# Atari_2600_PP.net
KiCad netlist of a schematic drawn in EAGLE
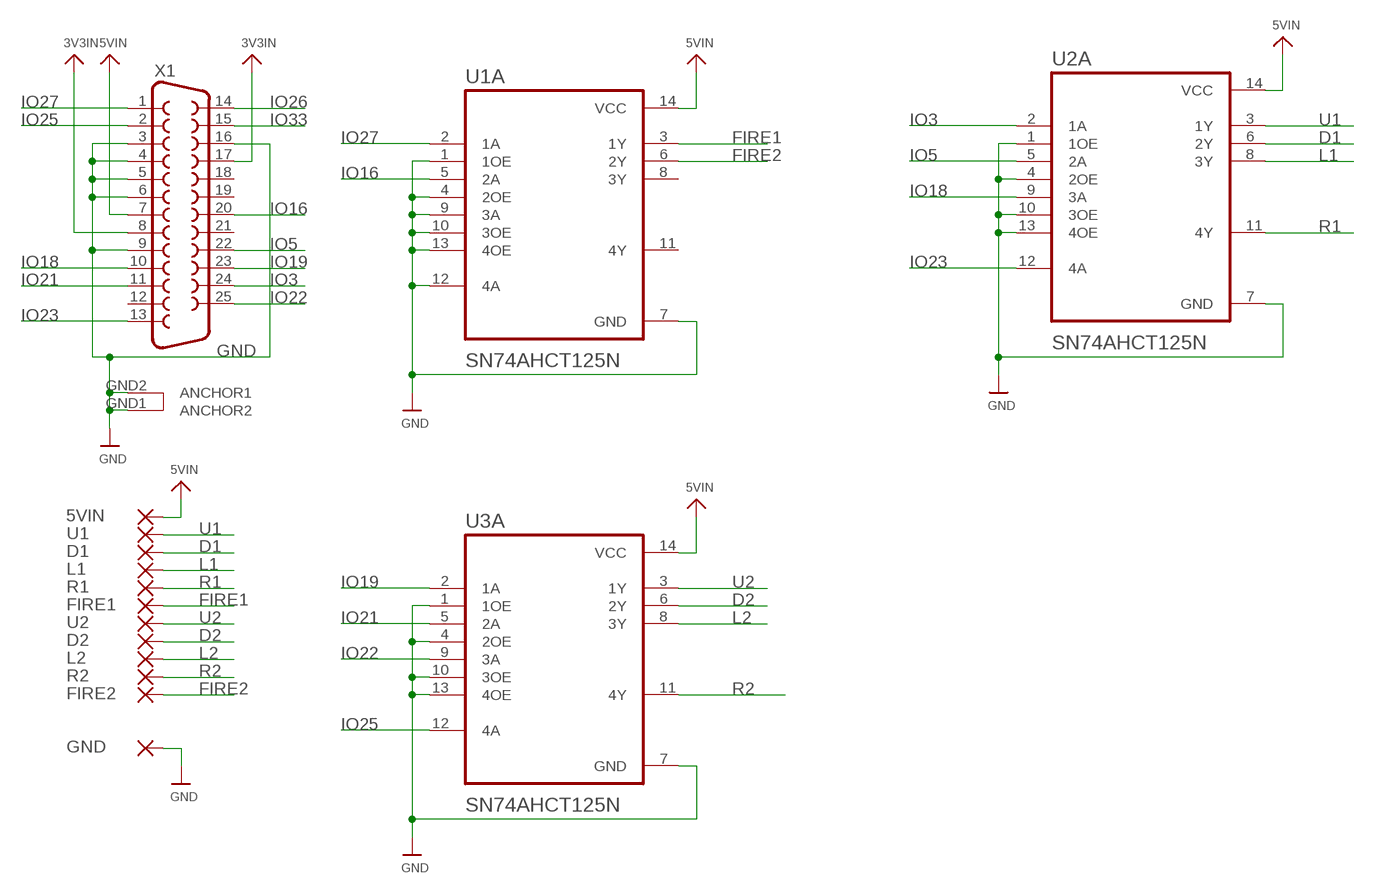
[diagram p0: schematic, sheet 1]

(export (version "E")
  (design (tool "Eeschema 10.0.6"))
  (components
    (comp (ref "5VIN")
      (value "SMD5")
      (footprint "eagle-import:SMD2,54-5,08")
      (libsource (lib "eagle-import") (part "SMD5"))
    )
    (comp (ref "D1")
      (value "SMD5")
      (footprint "eagle-import:SMD2,54-5,08")
      (libsource (lib "eagle-import") (part "SMD5"))
    )
    (comp (ref "D2")
      (value "SMD5")
      (footprint "eagle-import:SMD2,54-5,08")
      (libsource (lib "eagle-import") (part "SMD5"))
    )
    (comp (ref "FIRE1")
      (value "SMD5")
      (footprint "eagle-import:SMD2,54-5,08")
      (libsource (lib "eagle-import") (part "SMD5"))
    )
    (comp (ref "FIRE2")
      (value "SMD5")
      (footprint "eagle-import:SMD2,54-5,08")
      (libsource (lib "eagle-import") (part "SMD5"))
    )
    (comp (ref "GND")
      (value "SMD5")
      (footprint "eagle-import:SMD2,54-5,08")
      (libsource (lib "eagle-import") (part "SMD5"))
    )
    (comp (ref "L1")
      (value "SMD5")
      (footprint "eagle-import:SMD2,54-5,08")
      (libsource (lib "eagle-import") (part "SMD5"))
    )
    (comp (ref "L2")
      (value "SMD5")
      (footprint "eagle-import:SMD2,54-5,08")
      (libsource (lib "eagle-import") (part "SMD5"))
    )
    (comp (ref "R1")
      (value "SMD5")
      (footprint "eagle-import:SMD2,54-5,08")
      (libsource (lib "eagle-import") (part "SMD5"))
    )
    (comp (ref "R2")
      (value "SMD5")
      (footprint "eagle-import:SMD2,54-5,08")
      (libsource (lib "eagle-import") (part "SMD5"))
    )
    (comp (ref "U1")
      (value "SMD5")
      (footprint "eagle-import:SMD2,54-5,08")
      (libsource (lib "eagle-import") (part "SMD5"))
    )
    (comp (ref "U1A")
      (value "SN74AHCT125N")
      (footprint "eagle-import:DIP794W45P254L1969H508Q14")
      (fields (field (name "MF") "Texas Instruments"))
      (libsource (lib "eagle-import") (part "SN74AHCT125N"))
    )
    (comp (ref "U2")
      (value "SMD5")
      (footprint "eagle-import:SMD2,54-5,08")
      (libsource (lib "eagle-import") (part "SMD5"))
    )
    (comp (ref "U2A")
      (value "SN74AHCT125N")
      (footprint "eagle-import:DIP794W45P254L1969H508Q14")
      (fields (field (name "MF") "Texas Instruments"))
      (libsource (lib "eagle-import") (part "SN74AHCT125N"))
    )
    (comp (ref "U3A")
      (value "SN74AHCT125N")
      (footprint "eagle-import:DIP794W45P254L1969H508Q14")
      (fields (field (name "MF") "Texas Instruments"))
      (libsource (lib "eagle-import") (part "SN74AHCT125N"))
    )
    (comp (ref "X1")
      (value "DB25_FEMALEHP")
      (footprint "eagle-import:F25HP")
      (libsource (lib "eagle-import") (part "DB25_FEMALEHP"))
    )
  )
  (nets
    (net (code "1") (name "/D1") (class "Default")
      (node (ref "D1") (pin "1") (pinfunction "P_1") (pintype "passive"))
      (node (ref "U2A") (pin "6") (pinfunction "2Y_6") (pintype "output"))
    )
    (net (code "2") (name "/D2") (class "Default")
      (node (ref "D2") (pin "1") (pinfunction "P_1") (pintype "passive"))
      (node (ref "U3A") (pin "6") (pinfunction "2Y_6") (pintype "output"))
    )
    (net (code "3") (name "/FIRE1") (class "Default")
      (node (ref "FIRE1") (pin "1") (pinfunction "P_1") (pintype "passive"))
      (node (ref "U1A") (pin "3") (pinfunction "1Y_3") (pintype "output"))
    )
    (net (code "4") (name "/FIRE2") (class "Default")
      (node (ref "FIRE2") (pin "1") (pinfunction "P_1") (pintype "passive"))
      (node (ref "U1A") (pin "6") (pinfunction "2Y_6") (pintype "output"))
    )
    (net (code "5") (name "/IO3") (class "Default")
      (node (ref "U2A") (pin "2") (pinfunction "1A_2") (pintype "input"))
      (node (ref "X1") (pin "24") (pinfunction "24_24") (pintype "passive"))
    )
    (net (code "6") (name "/IO5") (class "Default")
      (node (ref "U2A") (pin "5") (pinfunction "2A_5") (pintype "input"))
      (node (ref "X1") (pin "22") (pinfunction "22_22") (pintype "passive"))
    )
    (net (code "7") (name "/IO16") (class "Default")
      (node (ref "U1A") (pin "5") (pinfunction "2A_5") (pintype "input"))
      (node (ref "X1") (pin "20") (pinfunction "20_20") (pintype "passive"))
    )
    (net (code "8") (name "/IO18") (class "Default")
      (node (ref "U2A") (pin "9") (pinfunction "3A_9") (pintype "input"))
      (node (ref "X1") (pin "10") (pinfunction "10_10") (pintype "passive"))
    )
    (net (code "9") (name "/IO19") (class "Default")
      (node (ref "U3A") (pin "2") (pinfunction "1A_2") (pintype "input"))
      (node (ref "X1") (pin "23") (pinfunction "23_23") (pintype "passive"))
    )
    (net (code "10") (name "/IO21") (class "Default")
      (node (ref "U3A") (pin "5") (pinfunction "2A_5") (pintype "input"))
      (node (ref "X1") (pin "11") (pinfunction "11_11") (pintype "passive"))
    )
    (net (code "11") (name "/IO22") (class "Default")
      (node (ref "U3A") (pin "9") (pinfunction "3A_9") (pintype "input"))
      (node (ref "X1") (pin "25") (pinfunction "25_25") (pintype "passive"))
    )
    (net (code "12") (name "/IO23") (class "Default")
      (node (ref "U2A") (pin "12") (pinfunction "4A_12") (pintype "bidirectional"))
      (node (ref "X1") (pin "13") (pinfunction "13_13") (pintype "passive"))
    )
    (net (code "13") (name "/IO25") (class "Default")
      (node (ref "U3A") (pin "12") (pinfunction "4A_12") (pintype "bidirectional"))
      (node (ref "X1") (pin "2") (pinfunction "2_2") (pintype "passive"))
    )
    (net (code "14") (name "/IO26") (class "Default")
      (node (ref "X1") (pin "14") (pinfunction "14_14") (pintype "passive"))
    )
    (net (code "15") (name "/IO27") (class "Default")
      (node (ref "U1A") (pin "2") (pinfunction "1A_2") (pintype "input"))
      (node (ref "X1") (pin "1") (pinfunction "1_1") (pintype "passive"))
    )
    (net (code "16") (name "/IO33") (class "Default")
      (node (ref "X1") (pin "15") (pinfunction "15_15") (pintype "passive"))
    )
    (net (code "17") (name "/L1") (class "Default")
      (node (ref "L1") (pin "1") (pinfunction "P_1") (pintype "passive"))
      (node (ref "U2A") (pin "8") (pinfunction "3Y_8") (pintype "output"))
    )
    (net (code "18") (name "/L2") (class "Default")
      (node (ref "L2") (pin "1") (pinfunction "P_1") (pintype "passive"))
      (node (ref "U3A") (pin "8") (pinfunction "3Y_8") (pintype "output"))
    )
    (net (code "19") (name "/R1") (class "Default")
      (node (ref "R1") (pin "1") (pinfunction "P_1") (pintype "passive"))
      (node (ref "U2A") (pin "11") (pinfunction "4Y_11") (pintype "output"))
    )
    (net (code "20") (name "/R2") (class "Default")
      (node (ref "R2") (pin "1") (pinfunction "P_1") (pintype "passive"))
      (node (ref "U3A") (pin "11") (pinfunction "4Y_11") (pintype "output"))
    )
    (net (code "21") (name "/U1") (class "Default")
      (node (ref "U1") (pin "1") (pinfunction "P_1") (pintype "passive"))
      (node (ref "U2A") (pin "3") (pinfunction "1Y_3") (pintype "output"))
    )
    (net (code "22") (name "/U2") (class "Default")
      (node (ref "U2") (pin "1") (pinfunction "P_1") (pintype "passive"))
      (node (ref "U3A") (pin "3") (pinfunction "1Y_3") (pintype "output"))
    )
    (net (code "23") (name "3V3IN") (class "Default")
      (node (ref "X1") (pin "17") (pinfunction "17_17") (pintype "passive"))
      (node (ref "X1") (pin "8") (pinfunction "8_8") (pintype "passive"))
    )
    (net (code "24") (name "5VIN") (class "Default")
      (node (ref "5VIN") (pin "1") (pinfunction "P_1") (pintype "passive"))
      (node (ref "U1A") (pin "14") (pinfunction "VCC_14") (pintype "power_in"))
      (node (ref "U2A") (pin "14") (pinfunction "VCC_14") (pintype "power_in"))
      (node (ref "U3A") (pin "14") (pinfunction "VCC_14") (pintype "power_in"))
      (node (ref "X1") (pin "7") (pinfunction "7_7") (pintype "passive"))
    )
    (net (code "25") (name "GND") (class "Default")
      (node (ref "GND") (pin "1") (pinfunction "P_1") (pintype "passive"))
      (node (ref "U1A") (pin "1") (pinfunction "1OE_1") (pintype "input"))
      (node (ref "U1A") (pin "10") (pinfunction "3OE_10") (pintype "input"))
      (node (ref "U1A") (pin "12") (pinfunction "4A_12") (pintype "bidirectional"))
      (node (ref "U1A") (pin "13") (pinfunction "4OE_13") (pintype "input"))
      (node (ref "U1A") (pin "4") (pinfunction "2OE_4") (pintype "input"))
      (node (ref "U1A") (pin "7") (pinfunction "GND_7") (pintype "power_in"))
      (node (ref "U1A") (pin "9") (pinfunction "3A_9") (pintype "input"))
      (node (ref "U2A") (pin "1") (pinfunction "1OE_1") (pintype "input"))
      (node (ref "U2A") (pin "10") (pinfunction "3OE_10") (pintype "input"))
      (node (ref "U2A") (pin "13") (pinfunction "4OE_13") (pintype "input"))
      (node (ref "U2A") (pin "4") (pinfunction "2OE_4") (pintype "input"))
      (node (ref "U2A") (pin "7") (pinfunction "GND_7") (pintype "power_in"))
      (node (ref "U3A") (pin "1") (pinfunction "1OE_1") (pintype "input"))
      (node (ref "U3A") (pin "10") (pinfunction "3OE_10") (pintype "input"))
      (node (ref "U3A") (pin "13") (pinfunction "4OE_13") (pintype "input"))
      (node (ref "U3A") (pin "4") (pinfunction "2OE_4") (pintype "input"))
      (node (ref "U3A") (pin "7") (pinfunction "GND_7") (pintype "power_in"))
      (node (ref "X1") (pin "16") (pinfunction "16_16") (pintype "passive"))
      (node (ref "X1") (pin "3") (pinfunction "3_3") (pintype "passive"))
      (node (ref "X1") (pin "4") (pinfunction "4_4") (pintype "passive"))
      (node (ref "X1") (pin "5") (pinfunction "5_5") (pintype "passive"))
      (node (ref "X1") (pin "6") (pinfunction "6_6") (pintype "passive"))
      (node (ref "X1") (pin "9") (pinfunction "9_9") (pintype "passive"))
      (node (ref "X1") (pin "GND1") (pinfunction "ANCHOR2_GND1") (pintype "bidirectional"))
      (node (ref "X1") (pin "GND2") (pinfunction "ANCHOR1_GND2") (pintype "bidirectional"))
    )
    (net (code "26") (name "unconnected-(U1A-3Y-Pad8)") (class "Default")
      (node (ref "U1A") (pin "8") (pinfunction "3Y_8") (pintype "output"))
    )
    (net (code "27") (name "unconnected-(U1A-4Y-Pad11)") (class "Default")
      (node (ref "U1A") (pin "11") (pinfunction "4Y_11") (pintype "output"))
    )
    (net (code "28") (name "unconnected-(X1-Pad12)") (class "Default")
      (node (ref "X1") (pin "12") (pinfunction "12_12") (pintype "passive"))
    )
    (net (code "29") (name "unconnected-(X1-Pad18)") (class "Default")
      (node (ref "X1") (pin "18") (pinfunction "18_18") (pintype "passive"))
    )
    (net (code "30") (name "unconnected-(X1-Pad19)") (class "Default")
      (node (ref "X1") (pin "19") (pinfunction "19_19") (pintype "passive"))
    )
    (net (code "31") (name "unconnected-(X1-Pad21)") (class "Default")
      (node (ref "X1") (pin "21") (pinfunction "21_21") (pintype "passive"))
    )
  )
)
